# Alim_Ticketing_Master.net
KiCad netlist of a schematic drawn in Altium Designer
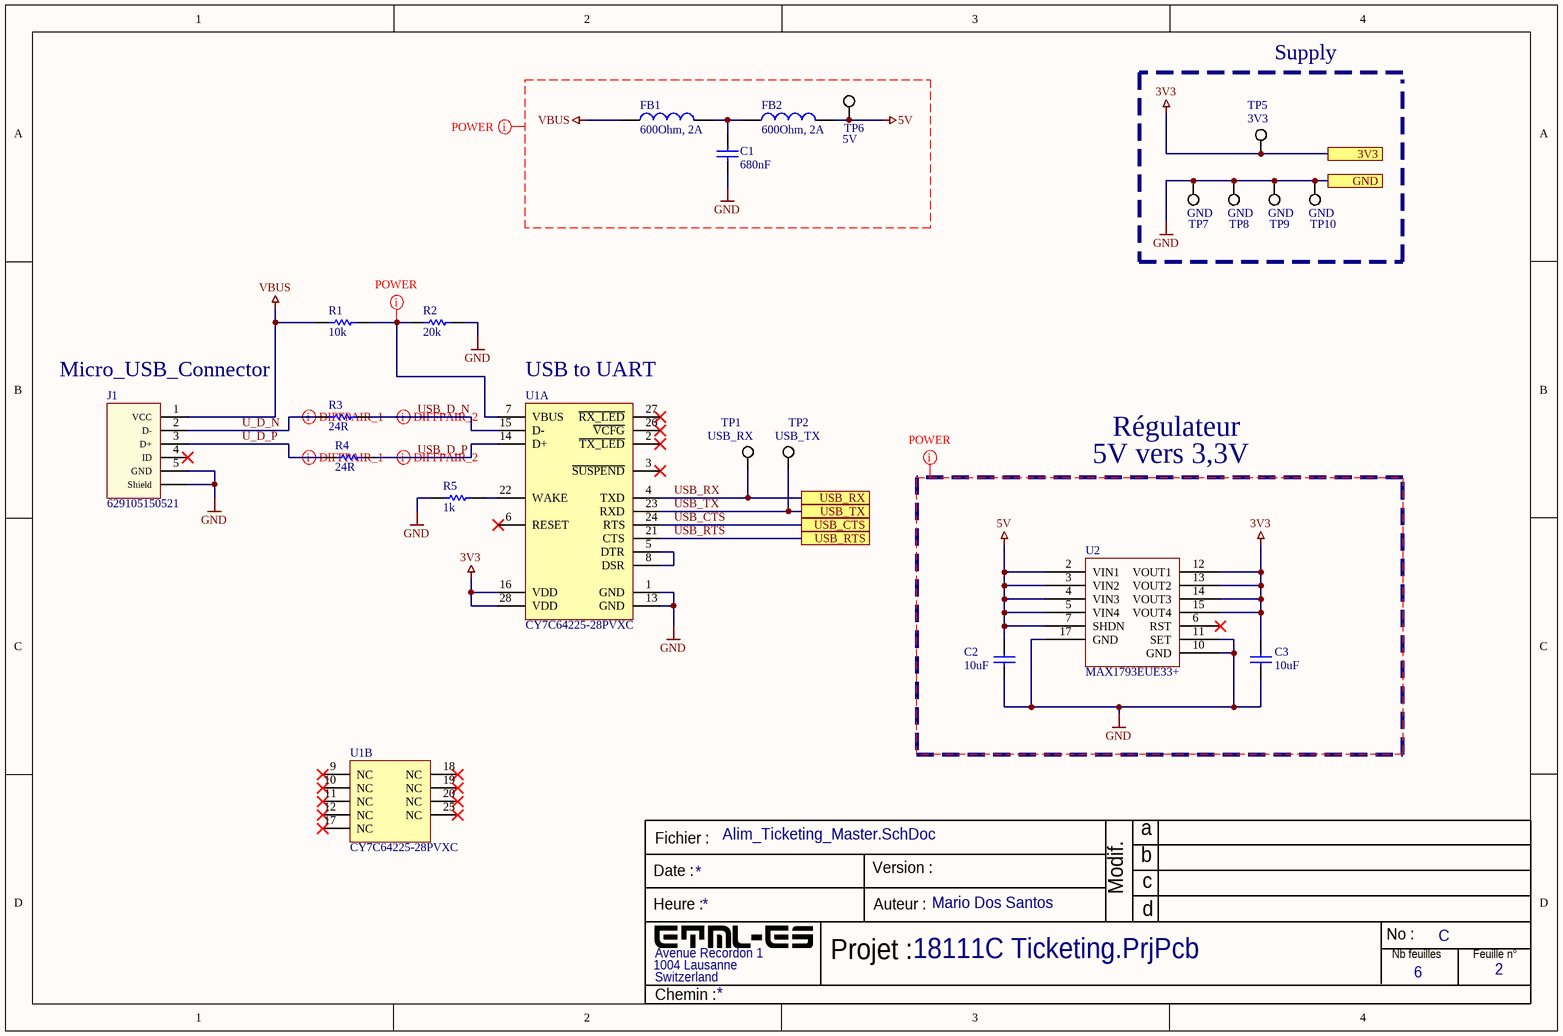
[diagram p0: Alim_Ticketing_Master.SchDoc]

(export (version "E")
  (design (tool "Eeschema 10.0.6"))
  (components
    (comp (ref "C1")
      (value "680nF")
      (footprint "6-0805_N")
      (description "WCAP-CSGP General Purpose Ceramic Capacitors, size 0805, 100nF, +/-10%, 50VDC")
      (libsource (lib "VPA_v2b") (part "885012207098"))
    )
    (comp (ref "C2")
      (value "10uF")
      (footprint "6-0805_N")
      (description "Capacitor")
      (fields (field (name "PUBLISHER") "Altium Limited"))
      (libsource (lib "Miscellaneous Devices") (part "Cap"))
    )
    (comp (ref "C3")
      (value "10uF")
      (footprint "6-0805_N")
      (description "Capacitor")
      (fields (field (name "PUBLISHER") "Altium Limited"))
      (libsource (lib "Miscellaneous Devices") (part "Cap"))
    )
    (comp (ref "FB1")
      (value "600Ohm, 2A")
      (footprint "WE-CBF_0805_High Current")
      (description "WE-CBF SMT EMI Suppression Ferrite Bead, size 0805, 600Ohm, 2A")
      (fields (field (name "PART NUMBER") "742792040") (field (name "PUBLISHER") "Wurth Elektronik"))
      (libsource (lib "VPA_v2b") (part "742792040"))
    )
    (comp (ref "FB2")
      (value "600Ohm, 2A")
      (footprint "WE-CBF_0805_High Current")
      (description "WE-CBF SMT EMI Suppression Ferrite Bead, size 0805, 600Ohm, 2A")
      (fields (field (name "PART NUMBER") "742792040") (field (name "PUBLISHER") "Wurth Elektronik"))
      (libsource (lib "VPA_v2b") (part "742792040"))
    )
    (comp (ref "J1")
      (value "629105150521")
      (footprint "629105150521")
      (description "Micro USB 2.0 SMT Type B Horizontal 5 Contacts High Current WR-COM")
      (fields (field (name "PART NUMBER") "732-5960-1-ND") (field (name "PUBLISHER") "Wurth Elektronik"))
      (libsource (lib "PCB_Ticketing_Slave") (part "629105150521"))
    )
    (comp (ref "R1")
      (value "10k")
      (footprint "RESC0805(2012)_L")
      (description "100K 0.125W 5% 0805 (2012 Metric)  SMD")
      (fields (field (name "TOLERANCE") "5 %") (field (name "POWER") "0.125 W"))
      (libsource (lib "Altium Content Vault") (part "CMP-1013-00122-1"))
    )
    (comp (ref "R2")
      (value "20k")
      (footprint "RESC0805(2012)_L")
      (description "100K 0.125W 5% 0805 (2012 Metric)  SMD")
      (fields (field (name "TOLERANCE") "5 %") (field (name "POWER") "0.125 W"))
      (libsource (lib "Altium Content Vault") (part "CMP-1013-00122-1"))
    )
    (comp (ref "R3")
      (value "24R")
      (footprint "RESC0805(2012)_L")
      (description "100K 0.125W 5% 0805 (2012 Metric)  SMD")
      (fields (field (name "TOLERANCE") "5 %") (field (name "POWER") "0.125 W"))
      (libsource (lib "Altium Content Vault") (part "CMP-1013-00122-1"))
    )
    (comp (ref "R4")
      (value "24R")
      (footprint "RESC0805(2012)_L")
      (description "100K 0.125W 5% 0805 (2012 Metric)  SMD")
      (fields (field (name "TOLERANCE") "5 %") (field (name "POWER") "0.125 W"))
      (libsource (lib "Altium Content Vault") (part "CMP-1013-00122-1"))
    )
    (comp (ref "R5")
      (value "1k")
      (footprint "RESC0805(2012)_L")
      (description "100K 0.125W 5% 0805 (2012 Metric)  SMD")
      (fields (field (name "TOLERANCE") "5 %") (field (name "POWER") "0.125 W"))
      (libsource (lib "Altium Content Vault") (part "CMP-1013-00122-1"))
    )
    (comp (ref "TP1")
      (value "~")
      (footprint "KSTN-5019_V")
      (description "Test Point, 1 Position SMD, RoHS, Tape and Reel")
      (libsource (lib "Altium Content Vault") (part "TESTPOINT_WHITE"))
    )
    (comp (ref "TP2")
      (value "~")
      (footprint "KSTN-5019_V")
      (description "Test Point, 1 Position SMD, RoHS, Tape and Reel")
      (libsource (lib "Altium Content Vault") (part "TESTPOINT_WHITE"))
    )
    (comp (ref "TP5")
      (value "~")
      (footprint "KSTN-5019_V")
      (description "Test Point, 1 Position SMD, RoHS, Tape and Reel")
      (libsource (lib "Altium Content Vault") (part "TESTPOINT_WHITE"))
    )
    (comp (ref "TP6")
      (value "~")
      (footprint "KSTN-5019_V")
      (description "Test Point, 1 Position SMD, RoHS, Tape and Reel")
      (libsource (lib "Altium Content Vault") (part "TESTPOINT_WHITE"))
    )
    (comp (ref "TP7")
      (value "~")
      (footprint "KSTN-5019_V")
      (description "Test Point, 1 Position SMD, RoHS, Tape and Reel")
      (libsource (lib "Altium Content Vault") (part "TESTPOINT_WHITE"))
    )
    (comp (ref "TP8")
      (value "~")
      (footprint "KSTN-5019_V")
      (description "Test Point, 1 Position SMD, RoHS, Tape and Reel")
      (libsource (lib "Altium Content Vault") (part "TESTPOINT_WHITE"))
    )
    (comp (ref "TP9")
      (value "~")
      (footprint "KSTN-5019_V")
      (description "Test Point, 1 Position SMD, RoHS, Tape and Reel")
      (libsource (lib "Altium Content Vault") (part "TESTPOINT_WHITE"))
    )
    (comp (ref "TP10")
      (value "~")
      (footprint "KSTN-5019_V")
      (description "Test Point, 1 Position SMD, RoHS, Tape and Reel")
      (libsource (lib "Altium Content Vault") (part "TESTPOINT_WHITE"))
    )
    (comp (ref "U1")
      (value "CY7C64225-28PVXC")
      (footprint "CYP-PVX28_N")
      (description "USB-to-UART Bridge Controller, 3 to 5.25 V, 0 to 70 degC, 28-Pin SSOP (PVX28), Tube")
      (fields (field (name "MANUFACTURER") "Cypress") (field (name "PART NUMBER") "428-3158-ND"))
      (libsource (lib "PCB_Ticketing_Slave") (part "CMP-0967-00143-1"))
    )
    (comp (ref "U2")
      (value "MAX1793EUE33+")
      (footprint "TSOP65P640X110_HS-17N")
      (libsource (lib "2018A_CarteIoEscapeRoom_CAD") (part "MAX1793"))
    )
  )
  (nets
    (net (code "1") (name "/USB_CTS") (class "Default")
      (node (ref "U1") (pin "24") (pinfunction "RTS_24") (pintype "passive"))
    )
    (net (code "2") (name "/USB_D_N") (class "Default")
      (node (ref "R3") (pin "2") (pinfunction "2_2") (pintype "passive"))
      (node (ref "U1") (pin "15") (pinfunction "D-_15") (pintype "passive"))
    )
    (net (code "3") (name "/USB_D_P") (class "Default")
      (node (ref "R4") (pin "2") (pinfunction "2_2") (pintype "passive"))
      (node (ref "U1") (pin "14") (pinfunction "D+_14") (pintype "passive"))
    )
    (net (code "4") (name "/USB_RTS") (class "Default")
      (node (ref "U1") (pin "21") (pinfunction "CTS_21") (pintype "passive"))
    )
    (net (code "5") (name "/USB_RX") (class "Default")
      (node (ref "TP1") (pin "1") (pinfunction "1_1") (pintype "passive"))
      (node (ref "U1") (pin "4") (pinfunction "TXD_4") (pintype "passive"))
    )
    (net (code "6") (name "/USB_TX") (class "Default")
      (node (ref "TP2") (pin "1") (pinfunction "1_1") (pintype "passive"))
      (node (ref "U1") (pin "23") (pinfunction "RXD_23") (pintype "passive"))
    )
    (net (code "7") (name "/U_D_N") (class "Default")
      (node (ref "J1") (pin "2") (pinfunction "D-_2") (pintype "passive"))
      (node (ref "R3") (pin "1") (pinfunction "1_1") (pintype "passive"))
    )
    (net (code "8") (name "/U_D_P") (class "Default")
      (node (ref "J1") (pin "3") (pinfunction "D+_3") (pintype "passive"))
      (node (ref "R4") (pin "1") (pinfunction "1_1") (pintype "passive"))
    )
    (net (code "9") (name "3V3") (class "Default")
      (node (ref "C3") (pin "2") (pinfunction "2_2") (pintype "passive"))
      (node (ref "TP5") (pin "1") (pinfunction "1_1") (pintype "passive"))
      (node (ref "U1") (pin "16") (pinfunction "VDD_16") (pintype "passive"))
      (node (ref "U1") (pin "28") (pinfunction "VDD_28") (pintype "passive"))
      (node (ref "U2") (pin "12") (pinfunction "VOUT1_12") (pintype "passive"))
      (node (ref "U2") (pin "13") (pinfunction "VOUT2_13") (pintype "passive"))
      (node (ref "U2") (pin "14") (pinfunction "VOUT3_14") (pintype "passive"))
      (node (ref "U2") (pin "15") (pinfunction "VOUT4_15") (pintype "passive"))
    )
    (net (code "10") (name "5V") (class "Default")
      (node (ref "C2") (pin "1") (pinfunction "1_1") (pintype "passive"))
      (node (ref "FB2") (pin "2") (pinfunction "2_2") (pintype "passive"))
      (node (ref "TP6") (pin "1") (pinfunction "1_1") (pintype "passive"))
      (node (ref "U2") (pin "2") (pinfunction "VIN1_2") (pintype "passive"))
      (node (ref "U2") (pin "3") (pinfunction "VIN2_3") (pintype "passive"))
      (node (ref "U2") (pin "4") (pinfunction "VIN3_4") (pintype "passive"))
      (node (ref "U2") (pin "5") (pinfunction "VIN4_5") (pintype "passive"))
      (node (ref "U2") (pin "7") (pinfunction "SHDN_7") (pintype "passive"))
    )
    (net (code "11") (name "GND") (class "Default")
      (node (ref "C1") (pin "2") (pinfunction "2_2") (pintype "passive"))
      (node (ref "C2") (pin "2") (pinfunction "2_2") (pintype "passive"))
      (node (ref "C3") (pin "1") (pinfunction "1_1") (pintype "passive"))
      (node (ref "J1") (pin "5") (pinfunction "GND_5") (pintype "passive"))
      (node (ref "J1") (pin "Shell") (pinfunction "Shield_Shell") (pintype "passive"))
      (node (ref "R2") (pin "2") (pinfunction "2_2") (pintype "passive"))
      (node (ref "R5") (pin "2") (pinfunction "2_2") (pintype "passive"))
      (node (ref "TP10") (pin "1") (pinfunction "1_1") (pintype "passive"))
      (node (ref "TP7") (pin "1") (pinfunction "1_1") (pintype "passive"))
      (node (ref "TP8") (pin "1") (pinfunction "1_1") (pintype "passive"))
      (node (ref "TP9") (pin "1") (pinfunction "1_1") (pintype "passive"))
      (node (ref "U1") (pin "1") (pinfunction "GND_1") (pintype "passive"))
      (node (ref "U1") (pin "13") (pinfunction "GND_13") (pintype "passive"))
      (node (ref "U2") (pin "10") (pinfunction "GND_10") (pintype "power_in"))
      (node (ref "U2") (pin "11") (pinfunction "SET_11") (pintype "passive"))
      (node (ref "U2") (pin "17") (pinfunction "GND_17") (pintype "power_in"))
    )
    (net (code "12") (name "Net-(C1-Pad1)") (class "Default")
      (node (ref "C1") (pin "1") (pinfunction "1_1") (pintype "passive"))
      (node (ref "FB1") (pin "2") (pinfunction "2_2") (pintype "passive"))
      (node (ref "FB2") (pin "1") (pinfunction "1_1") (pintype "passive"))
    )
    (net (code "13") (name "Net-(U1A-DSR)") (class "Default")
      (node (ref "U1") (pin "5") (pinfunction "DTR_5") (pintype "passive"))
      (node (ref "U1") (pin "8") (pinfunction "DSR_8") (pintype "passive"))
    )
    (net (code "14") (name "Net-(U1A-VBUS)") (class "Default")
      (node (ref "R1") (pin "2") (pinfunction "2_2") (pintype "passive"))
      (node (ref "R2") (pin "1") (pinfunction "1_1") (pintype "passive"))
      (node (ref "U1") (pin "7") (pinfunction "VBUS_7") (pintype "passive"))
    )
    (net (code "15") (name "Net-(U1A-WAKE)") (class "Default")
      (node (ref "R5") (pin "1") (pinfunction "1_1") (pintype "passive"))
      (node (ref "U1") (pin "22") (pinfunction "WAKE_22") (pintype "passive"))
    )
    (net (code "16") (name "VBUS") (class "Default")
      (node (ref "FB1") (pin "1") (pinfunction "1_1") (pintype "passive"))
      (node (ref "J1") (pin "1") (pinfunction "VCC_1") (pintype "passive"))
      (node (ref "R1") (pin "1") (pinfunction "1_1") (pintype "passive"))
    )
    (net (code "17") (name "unconnected-(J1-ID-Pad4)") (class "Default")
      (node (ref "J1") (pin "4") (pinfunction "ID_4") (pintype "passive+no_connect"))
    )
    (net (code "18") (name "unconnected-(U1A-RESET-Pad6)") (class "Default")
      (node (ref "U1") (pin "6") (pinfunction "RESET_6") (pintype "passive+no_connect"))
    )
    (net (code "19") (name "unconnected-(U1A-~{RX_LED}-Pad27)") (class "Default")
      (node (ref "U1") (pin "27") (pinfunction "~{RX_LED}_27") (pintype "passive+no_connect"))
    )
    (net (code "20") (name "unconnected-(U1A-~{SUSPEND}-Pad3)") (class "Default")
      (node (ref "U1") (pin "3") (pinfunction "~{SUSPEND}_3") (pintype "passive+no_connect"))
    )
    (net (code "21") (name "unconnected-(U1A-~{TX_LED}-Pad2)") (class "Default")
      (node (ref "U1") (pin "2") (pinfunction "~{TX_LED}_2") (pintype "passive+no_connect"))
    )
    (net (code "22") (name "unconnected-(U1A-~{VCFG}-Pad26)") (class "Default")
      (node (ref "U1") (pin "26") (pinfunction "~{VCFG}_26") (pintype "passive+no_connect"))
    )
    (net (code "23") (name "unconnected-(U1B-NC-Pad9)") (class "Default")
      (node (ref "U1") (pin "9") (pinfunction "NC_9") (pintype "passive+no_connect"))
    )
    (net (code "24") (name "unconnected-(U1B-NC-Pad10)") (class "Default")
      (node (ref "U1") (pin "10") (pinfunction "NC_10") (pintype "passive+no_connect"))
    )
    (net (code "25") (name "unconnected-(U1B-NC-Pad11)") (class "Default")
      (node (ref "U1") (pin "11") (pinfunction "NC_11") (pintype "passive+no_connect"))
    )
    (net (code "26") (name "unconnected-(U1B-NC-Pad12)") (class "Default")
      (node (ref "U1") (pin "12") (pinfunction "NC_12") (pintype "passive+no_connect"))
    )
    (net (code "27") (name "unconnected-(U1B-NC-Pad17)") (class "Default")
      (node (ref "U1") (pin "17") (pinfunction "NC_17") (pintype "passive+no_connect"))
    )
    (net (code "28") (name "unconnected-(U1B-NC-Pad18)") (class "Default")
      (node (ref "U1") (pin "18") (pinfunction "NC_18") (pintype "passive+no_connect"))
    )
    (net (code "29") (name "unconnected-(U1B-NC-Pad19)") (class "Default")
      (node (ref "U1") (pin "19") (pinfunction "NC_19") (pintype "passive+no_connect"))
    )
    (net (code "30") (name "unconnected-(U1B-NC-Pad20)") (class "Default")
      (node (ref "U1") (pin "20") (pinfunction "NC_20") (pintype "passive+no_connect"))
    )
    (net (code "31") (name "unconnected-(U1B-NC-Pad25)") (class "Default")
      (node (ref "U1") (pin "25") (pinfunction "NC_25") (pintype "passive+no_connect"))
    )
    (net (code "32") (name "unconnected-(U2-RST-Pad6)") (class "Default")
      (node (ref "U2") (pin "6") (pinfunction "RST_6") (pintype "passive+no_connect"))
    )
  )
)
